# Qwiic_pHat_for_Raspberry_Pi_v30.net
KiCad netlist of a schematic drawn in EAGLE
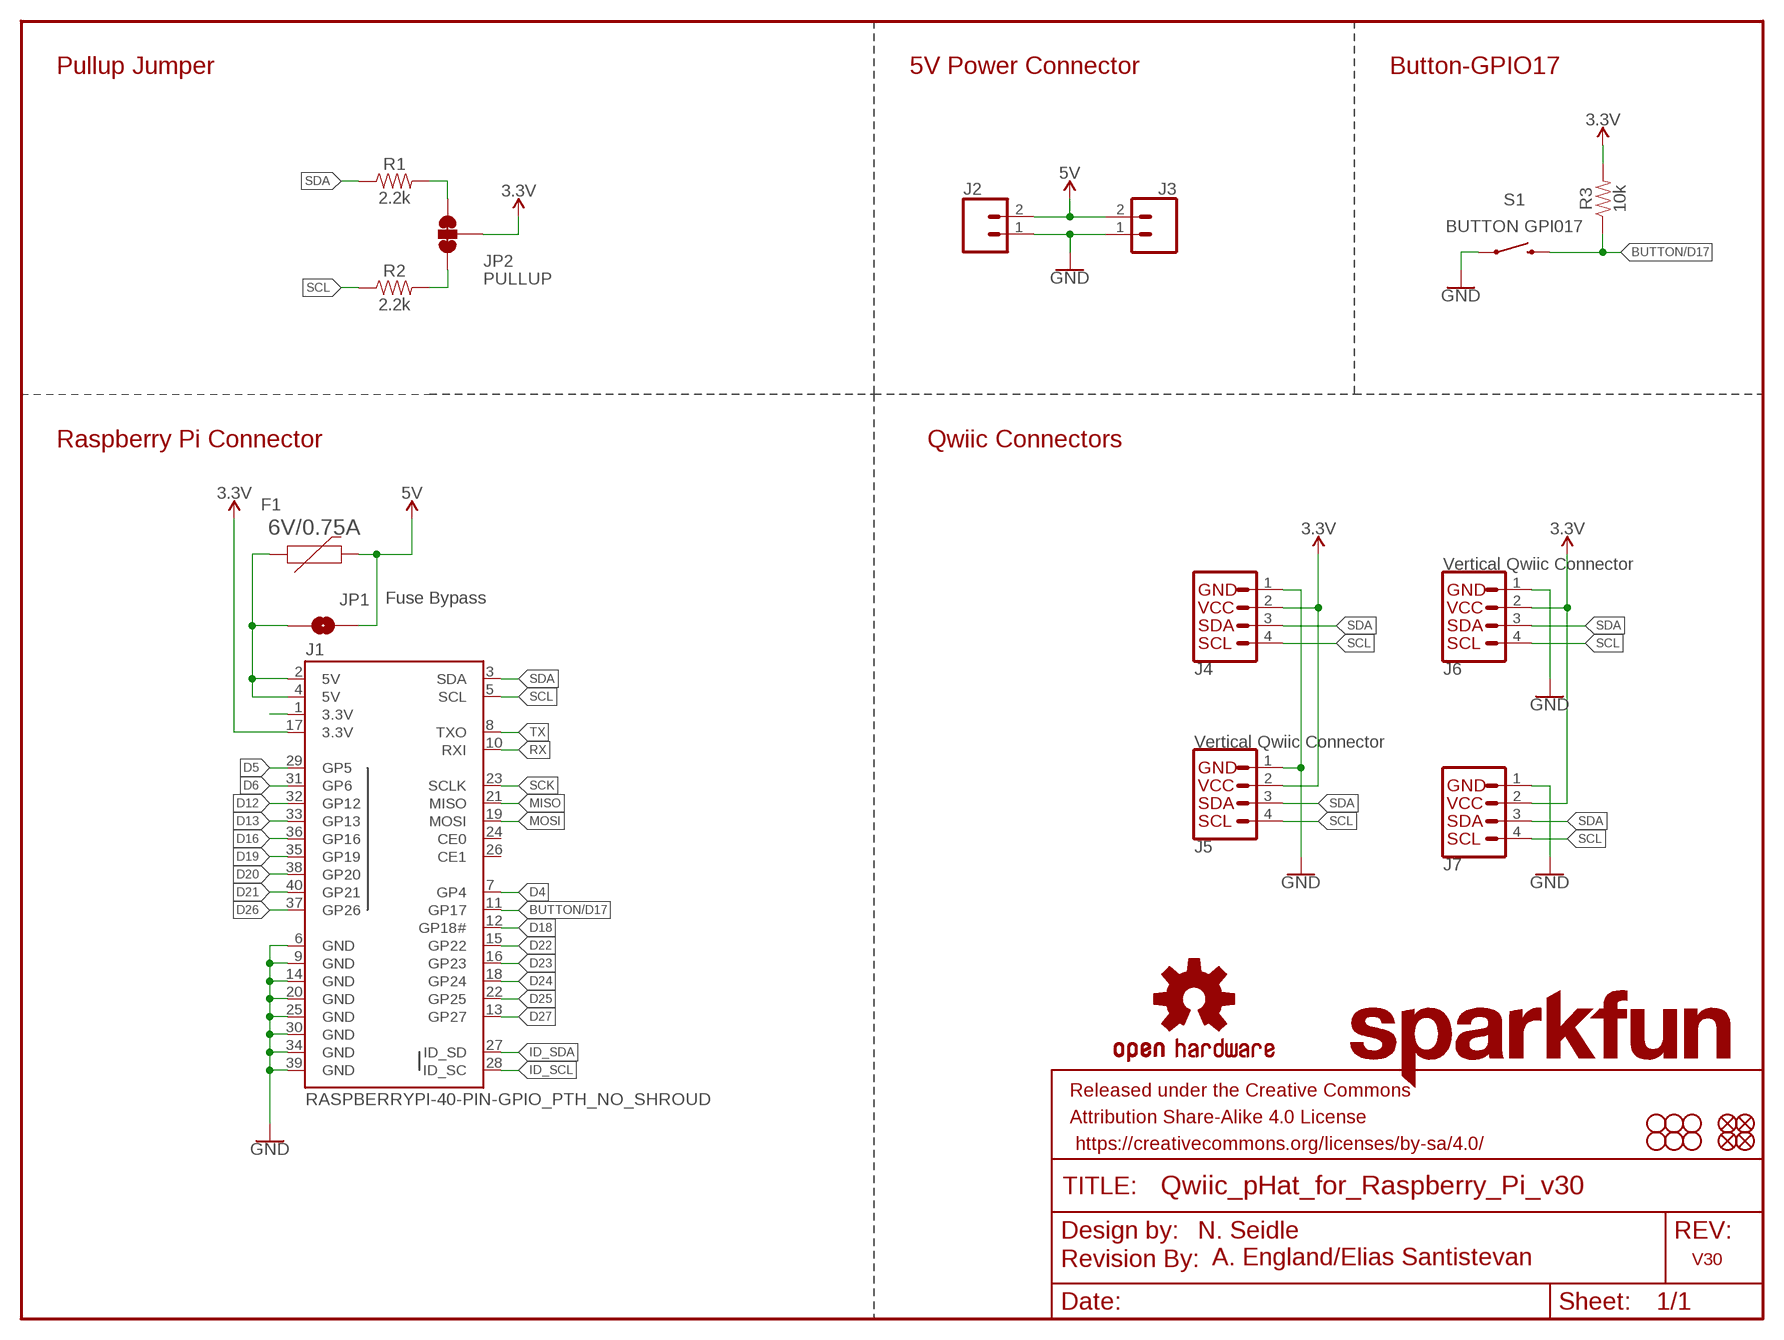
[diagram p0: schematic, sheet 1]

(export (version "E")
  (design (tool "Eeschema 10.0.6"))
  (components
    (comp (ref "F1")
      (value "6V/0.75A")
      (footprint "eagle-import:1206")
      (libsource (lib "eagle-import") (part "PPTC_0.75A"))
    )
    (comp (ref "FD1")
      (value "FIDUCIAL1X2")
      (footprint "eagle-import:FIDUCIAL-1X2")
      (libsource (lib "eagle-import") (part "FIDUCIAL1X2"))
    )
    (comp (ref "FD2")
      (value "FIDUCIAL1X2")
      (footprint "eagle-import:FIDUCIAL-1X2")
      (libsource (lib "eagle-import") (part "FIDUCIAL1X2"))
    )
    (comp (ref "FD3")
      (value "FIDUCIAL1X2")
      (footprint "eagle-import:FIDUCIAL-1X2")
      (libsource (lib "eagle-import") (part "FIDUCIAL1X2"))
    )
    (comp (ref "FD4")
      (value "FIDUCIAL1X2")
      (footprint "eagle-import:FIDUCIAL-1X2")
      (libsource (lib "eagle-import") (part "FIDUCIAL1X2"))
    )
    (comp (ref "FRAME1")
      (value "FRAME-LETTER")
      (footprint "eagle-import:CREATIVE_COMMONS")
      (libsource (lib "eagle-import") (part "FRAME-LETTER"))
    )
    (comp (ref "H1")
      (value "STAND-OFFTIGHT")
      (footprint "eagle-import:STAND-OFF-TIGHT")
      (libsource (lib "eagle-import") (part "STAND-OFFTIGHT"))
    )
    (comp (ref "H2")
      (value "STAND-OFFTIGHT")
      (footprint "eagle-import:STAND-OFF-TIGHT")
      (libsource (lib "eagle-import") (part "STAND-OFFTIGHT"))
    )
    (comp (ref "H3")
      (value "STAND-OFFTIGHT")
      (footprint "eagle-import:STAND-OFF-TIGHT")
      (libsource (lib "eagle-import") (part "STAND-OFFTIGHT"))
    )
    (comp (ref "H4")
      (value "STAND-OFFTIGHT")
      (footprint "eagle-import:STAND-OFF-TIGHT")
      (libsource (lib "eagle-import") (part "STAND-OFFTIGHT"))
    )
    (comp (ref "H5")
      (value "STAND-OFFTIGHT")
      (footprint "eagle-import:STAND-OFF-TIGHT")
      (libsource (lib "eagle-import") (part "STAND-OFFTIGHT"))
    )
    (comp (ref "H6")
      (value "STAND-OFFTIGHT")
      (footprint "eagle-import:STAND-OFF-TIGHT")
      (libsource (lib "eagle-import") (part "STAND-OFFTIGHT"))
    )
    (comp (ref "J1")
      (value "RASPBERRYPI-40-PIN-GPIO_PTH_NO_SHROUD")
      (footprint "eagle-import:2X20")
      (libsource (lib "eagle-import") (part "RASPBERRYPI-40-PIN-GPIO_PTH_NO_SHROUD"))
    )
    (comp (ref "J2")
      (value "CONN_023.5MM-NO_SILK")
      (footprint "eagle-import:SCREWTERMINAL-3.5MM-2-NS")
      (libsource (lib "eagle-import") (part "CONN_023.5MM-NO_SILK"))
    )
    (comp (ref "J3")
      (value "CONN_023.5MM")
      (footprint "eagle-import:SCREWTERMINAL-3.5MM-2")
      (libsource (lib "eagle-import") (part "CONN_023.5MM"))
    )
    (comp (ref "J4")
      (value "Qwiic Right Angle")
      (footprint "eagle-import:JST04_1MM_RA")
      (libsource (lib "eagle-import") (part "I2C_STANDARDQWIIC"))
    )
    (comp (ref "J5")
      (value "Vertical Qwiic Connector")
      (footprint "eagle-import:JST04_1MM_VERT")
      (libsource (lib "eagle-import") (part "QWIIC_CONNECTOR"))
    )
    (comp (ref "J6")
      (value "Vertical Qwiic Connector")
      (footprint "eagle-import:JST04_1MM_VERT")
      (libsource (lib "eagle-import") (part "QWIIC_CONNECTOR"))
    )
    (comp (ref "J7")
      (value "Qwiic Right Angle")
      (footprint "eagle-import:JST04_1MM_RA")
      (libsource (lib "eagle-import") (part "I2C_STANDARDQWIIC"))
    )
    (comp (ref "JP1")
      (value "JUMPER-SMT_2_NO_SILK")
      (footprint "eagle-import:SMT-JUMPER_2_NO_SILK")
      (libsource (lib "eagle-import") (part "JUMPER-SMT_2_NO_SILK"))
    )
    (comp (ref "JP2")
      (value "PULLUP")
      (footprint "eagle-import:SMT-JUMPER_3_2-NC_TRACE_NO-SILK")
      (libsource (lib "eagle-import") (part "JUMPER-SMT_3_2-NC_TRACE_NO-SILK"))
    )
    (comp (ref "LOGO1")
      (value "REVISION")
      (footprint "eagle-import:REVISION")
      (libsource (lib "eagle-import") (part "REVISION"))
    )
    (comp (ref "LOGO2")
      (value "OSHW-LOGOS")
      (footprint "eagle-import:OSHW-LOGO-S")
      (libsource (lib "eagle-import") (part "OSHW-LOGOS"))
    )
    (comp (ref "LOGO3")
      (value "SFE_LOGO_NAME.1_INCH")
      (footprint "eagle-import:SFE_LOGO_NAME_.1")
      (libsource (lib "eagle-import") (part "SFE_LOGO_NAME.1_INCH"))
    )
    (comp (ref "R1")
      (value "2.2k")
      (footprint "eagle-import:0603")
      (libsource (lib "eagle-import") (part "2.2KOHM-0603-1/10W-1%"))
    )
    (comp (ref "R2")
      (value "2.2k")
      (footprint "eagle-import:0603")
      (libsource (lib "eagle-import") (part "2.2KOHM-0603-1/10W-1%"))
    )
    (comp (ref "R3")
      (value "10k")
      (footprint "eagle-import:0603")
      (libsource (lib "eagle-import") (part "10KOHM-0603-1/10W-1%"))
    )
    (comp (ref "S1")
      (value "BUTTON GPI017")
      (footprint "eagle-import:TACTILE_SWITCH_SMD_5.2MM")
      (libsource (lib "eagle-import") (part "MOMENTARY-SWITCH-SPST-SMD-5.2MM-TALL"))
    )
  )
  (nets
    (net (code "1") (name "3.3V") (class "Default")
      (node (ref "J1") (pin "17") (pinfunction "3.3V_17") (pintype "power_in"))
      (node (ref "J4") (pin "2") (pinfunction "2_2") (pintype "power_in"))
      (node (ref "J5") (pin "2") (pinfunction "2_2") (pintype "power_in"))
      (node (ref "J6") (pin "2") (pinfunction "2_2") (pintype "power_in"))
      (node (ref "J7") (pin "2") (pinfunction "2_2") (pintype "power_in"))
      (node (ref "JP2") (pin "2") (pinfunction "2_2") (pintype "passive"))
      (node (ref "R3") (pin "2") (pinfunction "2_2") (pintype "passive"))
    )
    (net (code "2") (name "5V") (class "Default")
      (node (ref "F1") (pin "2") (pinfunction "2_2") (pintype "bidirectional"))
      (node (ref "J2") (pin "2") (pinfunction "2_2") (pintype "passive"))
      (node (ref "J3") (pin "2") (pinfunction "2_2") (pintype "passive"))
      (node (ref "JP1") (pin "2") (pinfunction "2_2") (pintype "passive"))
    )
    (net (code "3") (name "BUTTON{slash}D17") (class "Default")
      (node (ref "J1") (pin "11") (pinfunction "GP17_11") (pintype "bidirectional"))
      (node (ref "R3") (pin "1") (pinfunction "1_1") (pintype "passive"))
      (node (ref "S1") (pin "3") (pinfunction "2_3") (pintype "passive"))
    )
    (net (code "4") (name "D4") (class "Default")
      (node (ref "J1") (pin "7") (pinfunction "GP4_7") (pintype "bidirectional"))
    )
    (net (code "5") (name "D5") (class "Default")
      (node (ref "J1") (pin "29") (pinfunction "GP5_29") (pintype "bidirectional"))
    )
    (net (code "6") (name "D6") (class "Default")
      (node (ref "J1") (pin "31") (pinfunction "GP6_31") (pintype "bidirectional"))
    )
    (net (code "7") (name "D12") (class "Default")
      (node (ref "J1") (pin "32") (pinfunction "GP12_32") (pintype "bidirectional"))
    )
    (net (code "8") (name "D13") (class "Default")
      (node (ref "J1") (pin "33") (pinfunction "GP13_33") (pintype "bidirectional"))
    )
    (net (code "9") (name "D16") (class "Default")
      (node (ref "J1") (pin "36") (pinfunction "GP16_36") (pintype "bidirectional"))
    )
    (net (code "10") (name "D18") (class "Default")
      (node (ref "J1") (pin "12") (pinfunction "GP18#_12") (pintype "bidirectional"))
    )
    (net (code "11") (name "D19") (class "Default")
      (node (ref "J1") (pin "35") (pinfunction "GP19_35") (pintype "bidirectional"))
    )
    (net (code "12") (name "D20") (class "Default")
      (node (ref "J1") (pin "38") (pinfunction "GP20_38") (pintype "bidirectional"))
    )
    (net (code "13") (name "D21") (class "Default")
      (node (ref "J1") (pin "40") (pinfunction "GP21_40") (pintype "bidirectional"))
    )
    (net (code "14") (name "D22") (class "Default")
      (node (ref "J1") (pin "15") (pinfunction "GP22_15") (pintype "bidirectional"))
    )
    (net (code "15") (name "D23") (class "Default")
      (node (ref "J1") (pin "16") (pinfunction "GP23_16") (pintype "bidirectional"))
    )
    (net (code "16") (name "D24") (class "Default")
      (node (ref "J1") (pin "18") (pinfunction "GP24_18") (pintype "bidirectional"))
    )
    (net (code "17") (name "D25") (class "Default")
      (node (ref "J1") (pin "22") (pinfunction "GP25_22") (pintype "bidirectional"))
    )
    (net (code "18") (name "D26") (class "Default")
      (node (ref "J1") (pin "37") (pinfunction "GP26_37") (pintype "bidirectional"))
    )
    (net (code "19") (name "D27") (class "Default")
      (node (ref "J1") (pin "13") (pinfunction "GP27_13") (pintype "bidirectional"))
    )
    (net (code "20") (name "GND") (class "Default")
      (node (ref "J1") (pin "14") (pinfunction "GND_14") (pintype "power_in"))
      (node (ref "J1") (pin "20") (pinfunction "GND_20") (pintype "power_in"))
      (node (ref "J1") (pin "25") (pinfunction "GND_25") (pintype "power_in"))
      (node (ref "J1") (pin "30") (pinfunction "GND_30") (pintype "power_in"))
      (node (ref "J1") (pin "34") (pinfunction "GND_34") (pintype "power_in"))
      (node (ref "J1") (pin "39") (pinfunction "GND_39") (pintype "power_in"))
      (node (ref "J1") (pin "6") (pinfunction "GND_6") (pintype "power_in"))
      (node (ref "J1") (pin "9") (pinfunction "GND_9") (pintype "power_in"))
      (node (ref "J2") (pin "1") (pinfunction "1_1") (pintype "passive"))
      (node (ref "J3") (pin "1") (pinfunction "1_1") (pintype "passive"))
      (node (ref "J4") (pin "1") (pinfunction "1_1") (pintype "power_in"))
      (node (ref "J5") (pin "1") (pinfunction "1_1") (pintype "power_in"))
      (node (ref "J6") (pin "1") (pinfunction "1_1") (pintype "power_in"))
      (node (ref "J7") (pin "1") (pinfunction "1_1") (pintype "power_in"))
      (node (ref "S1") (pin "1") (pinfunction "1_1") (pintype "passive"))
    )
    (net (code "21") (name "ID_SCL") (class "Default")
      (node (ref "J1") (pin "28") (pinfunction "ID_SC_28") (pintype "bidirectional"))
    )
    (net (code "22") (name "ID_SDA") (class "Default")
      (node (ref "J1") (pin "27") (pinfunction "ID_SD_27") (pintype "bidirectional"))
    )
    (net (code "23") (name "MISO") (class "Default")
      (node (ref "J1") (pin "21") (pinfunction "MISO_21") (pintype "input"))
    )
    (net (code "24") (name "MOSI") (class "Default")
      (node (ref "J1") (pin "19") (pinfunction "MOSI_19") (pintype "output"))
    )
    (net (code "25") (name "Net-(F1-Pad1)") (class "Default")
      (node (ref "F1") (pin "1") (pinfunction "1_1") (pintype "bidirectional"))
      (node (ref "J1") (pin "2") (pinfunction "5V_2") (pintype "power_in"))
      (node (ref "J1") (pin "4") (pinfunction "5V_4") (pintype "power_in"))
      (node (ref "JP1") (pin "1") (pinfunction "1_1") (pintype "passive"))
    )
    (net (code "26") (name "Net-(JP2-Pad1)") (class "Default")
      (node (ref "JP2") (pin "1") (pinfunction "1_1") (pintype "passive"))
      (node (ref "R2") (pin "2") (pinfunction "2_2") (pintype "passive"))
    )
    (net (code "27") (name "Net-(JP2-Pad3)") (class "Default")
      (node (ref "JP2") (pin "3") (pinfunction "3_3") (pintype "passive"))
      (node (ref "R1") (pin "2") (pinfunction "2_2") (pintype "passive"))
    )
    (net (code "28") (name "RX") (class "Default")
      (node (ref "J1") (pin "10") (pinfunction "RXI_10") (pintype "input"))
    )
    (net (code "29") (name "SCK") (class "Default")
      (node (ref "J1") (pin "23") (pinfunction "SCLK_23") (pintype "output"))
    )
    (net (code "30") (name "SCL") (class "Default")
      (node (ref "J1") (pin "5") (pinfunction "SCL_5") (pintype "bidirectional"))
      (node (ref "J4") (pin "4") (pinfunction "4_4") (pintype "passive"))
      (node (ref "J5") (pin "4") (pinfunction "4_4") (pintype "passive"))
      (node (ref "J6") (pin "4") (pinfunction "4_4") (pintype "passive"))
      (node (ref "J7") (pin "4") (pinfunction "4_4") (pintype "passive"))
      (node (ref "R2") (pin "1") (pinfunction "1_1") (pintype "passive"))
    )
    (net (code "31") (name "SDA") (class "Default")
      (node (ref "J1") (pin "3") (pinfunction "SDA_3") (pintype "bidirectional"))
      (node (ref "J4") (pin "3") (pinfunction "3_3") (pintype "passive"))
      (node (ref "J5") (pin "3") (pinfunction "3_3") (pintype "passive"))
      (node (ref "J6") (pin "3") (pinfunction "3_3") (pintype "passive"))
      (node (ref "J7") (pin "3") (pinfunction "3_3") (pintype "passive"))
      (node (ref "R1") (pin "1") (pinfunction "1_1") (pintype "passive"))
    )
    (net (code "32") (name "TX") (class "Default")
      (node (ref "J1") (pin "8") (pinfunction "TXO_8") (pintype "output"))
    )
    (net (code "33") (name "unconnected-(J1-3.3V-Pad1)") (class "Default")
      (node (ref "J1") (pin "1") (pinfunction "3.3V_1") (pintype "power_in"))
    )
    (net (code "34") (name "unconnected-(J1-CE0-Pad24)") (class "Default")
      (node (ref "J1") (pin "24") (pinfunction "CE0_24") (pintype "output"))
    )
    (net (code "35") (name "unconnected-(J1-CE1-Pad26)") (class "Default")
      (node (ref "J1") (pin "26") (pinfunction "CE1_26") (pintype "output"))
    )
  )
)
